# 01_Panel.net
KiCad netlist of a schematic drawn in Altium Designer
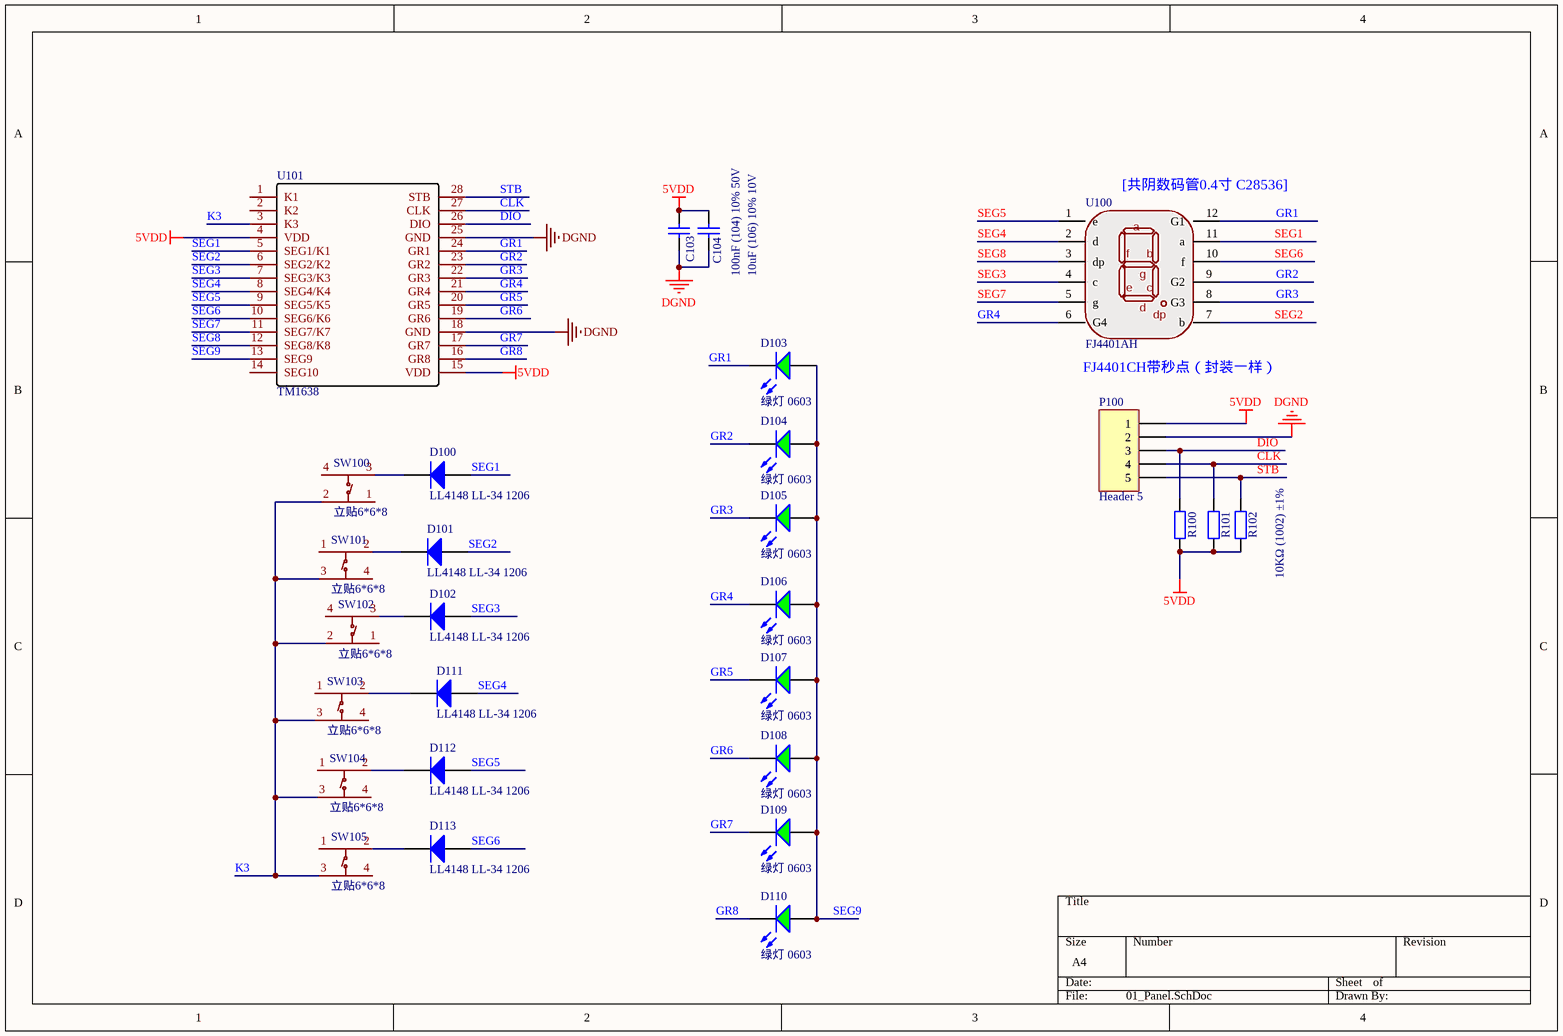
[diagram p0: 01_Panel.SchDoc]

(export (version "E")
  (design (tool "Eeschema 10.0.6"))
  (components
    (comp (ref "C103")
      (value "10uF (106) 10% 10V")
      (footprint "0603_C")
      (description "贴片电容")
      (libsource (lib "Miscellaneous Devices LC") (part "0603 10uF (106) 10% 10V"))
    )
    (comp (ref "C104")
      (value "100nF (104) 10% 50V")
      (footprint "0603_C")
      (description "贴片电容")
      (libsource (lib "Miscellaneous Devices LC") (part "0603 100nF (104) 10% 50V"))
    )
    (comp (ref "D100")
      (value "LL4148 LL-34 1206")
      (footprint "LL-34")
      (description "开关二极管")
      (libsource (lib "Miscellaneous Devices LC") (part "LL-34 LL4148 LL-34 1206"))
    )
    (comp (ref "D101")
      (value "LL4148 LL-34 1206")
      (footprint "LL-34")
      (description "开关二极管")
      (libsource (lib "Miscellaneous Devices LC") (part "LL-34 LL4148 LL-34 1206"))
    )
    (comp (ref "D102")
      (value "LL4148 LL-34 1206")
      (footprint "LL-34")
      (description "开关二极管")
      (libsource (lib "Miscellaneous Devices LC") (part "LL-34 LL4148 LL-34 1206"))
    )
    (comp (ref "D103")
      (value "绿灯 0603")
      (footprint "LED插件--3mm")
      (description "发光二极管")
      (libsource (lib "Miscellaneous Devices LC") (part "0603 绿灯"))
    )
    (comp (ref "D104")
      (value "绿灯 0603")
      (footprint "LED插件--3mm")
      (description "发光二极管")
      (libsource (lib "Miscellaneous Devices LC") (part "0603 绿灯"))
    )
    (comp (ref "D105")
      (value "绿灯 0603")
      (footprint "LED插件--3mm")
      (description "发光二极管")
      (libsource (lib "Miscellaneous Devices LC") (part "0603 绿灯"))
    )
    (comp (ref "D106")
      (value "绿灯 0603")
      (footprint "LED插件--3mm")
      (description "发光二极管")
      (libsource (lib "Miscellaneous Devices LC") (part "0603 绿灯"))
    )
    (comp (ref "D107")
      (value "绿灯 0603")
      (footprint "LED插件--3mm")
      (description "发光二极管")
      (libsource (lib "Miscellaneous Devices LC") (part "0603 绿灯"))
    )
    (comp (ref "D108")
      (value "绿灯 0603")
      (footprint "LED插件--3mm")
      (description "发光二极管")
      (libsource (lib "Miscellaneous Devices LC") (part "0603 绿灯"))
    )
    (comp (ref "D109")
      (value "绿灯 0603")
      (footprint "LED插件--3mm")
      (description "发光二极管")
      (libsource (lib "Miscellaneous Devices LC") (part "0603 绿灯"))
    )
    (comp (ref "D110")
      (value "绿灯 0603")
      (footprint "LED插件--3mm")
      (description "发光二极管")
      (libsource (lib "Miscellaneous Devices LC") (part "0603 绿灯"))
    )
    (comp (ref "D111")
      (value "LL4148 LL-34 1206")
      (footprint "LL-34")
      (description "开关二极管")
      (libsource (lib "Miscellaneous Devices LC") (part "LL-34 LL4148 LL-34 1206"))
    )
    (comp (ref "D112")
      (value "LL4148 LL-34 1206")
      (footprint "LL-34")
      (description "开关二极管")
      (libsource (lib "Miscellaneous Devices LC") (part "LL-34 LL4148 LL-34 1206"))
    )
    (comp (ref "D113")
      (value "LL4148 LL-34 1206")
      (footprint "LL-34")
      (description "开关二极管")
      (libsource (lib "Miscellaneous Devices LC") (part "LL-34 LL4148 LL-34 1206"))
    )
    (comp (ref "P100")
      (value "Header 5")
      (footprint "XH2.54-5P")
      (description "Header, 5-Pin")
      (fields (field (name "PUBLISHER") "Altium Limited"))
      (libsource (lib "Miscellaneous Connectors") (part "Header 5"))
    )
    (comp (ref "R100")
      (value "10KΩ (1002) ±1%")
      (footprint "0603_R")
      (description "贴片电阻")
      (libsource (lib "Miscellaneous Devices LC") (part "0603 10KΩ (1002) 1%"))
    )
    (comp (ref "R101")
      (value "10KΩ (1002) ±1%")
      (footprint "0603_R")
      (description "贴片电阻")
      (libsource (lib "Miscellaneous Devices LC") (part "0603 10KΩ (1002) 1%"))
    )
    (comp (ref "R102")
      (value "10KΩ (1002) ±1%")
      (footprint "0603_R")
      (description "贴片电阻")
      (libsource (lib "Miscellaneous Devices LC") (part "0603 10KΩ (1002) 1%"))
    )
    (comp (ref "SW100") (value "立贴6*6*8") (footprint "SW") (libsource (lib "RayPCB20210502") (part "SW")))
    (comp (ref "SW101") (value "立贴6*6*8") (footprint "SW") (libsource (lib "RayPCB20210502") (part "SW")))
    (comp (ref "SW102") (value "立贴6*6*8") (footprint "SW") (libsource (lib "RayPCB20210502") (part "SW")))
    (comp (ref "SW103") (value "立贴6*6*8") (footprint "SW") (libsource (lib "RayPCB20210502") (part "SW")))
    (comp (ref "SW104") (value "立贴6*6*8") (footprint "SW") (libsource (lib "RayPCB20210502") (part "SW")))
    (comp (ref "SW105") (value "立贴6*6*8") (footprint "SW") (libsource (lib "RayPCB20210502") (part "SW")))
    (comp (ref "U100")
      (value "FJ4401AH")
      (footprint "Digital_0.4")
      (libsource (lib "Schlibv2") (part "Digital_0.4"))
    )
    (comp (ref "U101") (value "TM1638") (footprint "TM1638") (libsource (lib "Schlibv2") (part "TM1638")))
  )
  (nets
    (net (code "1") (name "/CLK") (class "Default")
      (node (ref "P100") (pin "4") (pinfunction "4_4") (pintype "passive"))
      (node (ref "R101") (pin "2") (pinfunction "2_2") (pintype "passive"))
      (node (ref "U101") (pin "27") (pinfunction "CLK_27") (pintype "passive"))
    )
    (net (code "2") (name "/DIO") (class "Default")
      (node (ref "P100") (pin "3") (pinfunction "3_3") (pintype "passive"))
      (node (ref "R100") (pin "2") (pinfunction "2_2") (pintype "passive"))
      (node (ref "U101") (pin "26") (pinfunction "DIO_26") (pintype "passive"))
    )
    (net (code "3") (name "/GR1") (class "Default")
      (node (ref "D103") (pin "K") (pinfunction "K_K") (pintype "passive"))
      (node (ref "U100") (pin "12") (pinfunction "G1_12") (pintype "passive"))
      (node (ref "U101") (pin "24") (pinfunction "GR1_24") (pintype "passive"))
    )
    (net (code "4") (name "/GR2") (class "Default")
      (node (ref "D104") (pin "K") (pinfunction "K_K") (pintype "passive"))
      (node (ref "U100") (pin "9") (pinfunction "G2_9") (pintype "passive"))
      (node (ref "U101") (pin "23") (pinfunction "GR2_23") (pintype "passive"))
    )
    (net (code "5") (name "/GR3") (class "Default")
      (node (ref "D105") (pin "K") (pinfunction "K_K") (pintype "passive"))
      (node (ref "U100") (pin "8") (pinfunction "G3_8") (pintype "passive"))
      (node (ref "U101") (pin "22") (pinfunction "GR3_22") (pintype "passive"))
    )
    (net (code "6") (name "/GR4") (class "Default")
      (node (ref "D106") (pin "K") (pinfunction "K_K") (pintype "passive"))
      (node (ref "U100") (pin "6") (pinfunction "G4_6") (pintype "passive"))
      (node (ref "U101") (pin "21") (pinfunction "GR4_21") (pintype "passive"))
    )
    (net (code "7") (name "/GR5") (class "Default")
      (node (ref "D107") (pin "K") (pinfunction "K_K") (pintype "passive"))
      (node (ref "U101") (pin "20") (pinfunction "GR5_20") (pintype "passive"))
    )
    (net (code "8") (name "/GR6") (class "Default")
      (node (ref "D108") (pin "K") (pinfunction "K_K") (pintype "passive"))
      (node (ref "U101") (pin "19") (pinfunction "GR6_19") (pintype "passive"))
    )
    (net (code "9") (name "/GR7") (class "Default")
      (node (ref "D109") (pin "K") (pinfunction "K_K") (pintype "passive"))
      (node (ref "U101") (pin "17") (pinfunction "GR7_17") (pintype "passive"))
    )
    (net (code "10") (name "/GR8") (class "Default")
      (node (ref "D110") (pin "K") (pinfunction "K_K") (pintype "passive"))
      (node (ref "U101") (pin "16") (pinfunction "GR8_16") (pintype "passive"))
    )
    (net (code "11") (name "/K3") (class "Default")
      (node (ref "SW100") (pin "2") (pinfunction "2_2") (pintype "passive"))
      (node (ref "SW101") (pin "3") (pinfunction "3_3") (pintype "passive"))
      (node (ref "SW102") (pin "2") (pinfunction "2_2") (pintype "passive"))
      (node (ref "SW103") (pin "3") (pinfunction "3_3") (pintype "passive"))
      (node (ref "SW104") (pin "3") (pinfunction "3_3") (pintype "passive"))
      (node (ref "SW105") (pin "3") (pinfunction "3_3") (pintype "passive"))
      (node (ref "U101") (pin "3") (pinfunction "K3_3") (pintype "passive"))
    )
    (net (code "12") (name "/SEG1") (class "Default")
      (node (ref "D100") (pin "1") (pinfunction "A_1") (pintype "passive"))
      (node (ref "U100") (pin "11") (pinfunction "a_11") (pintype "passive"))
      (node (ref "U101") (pin "5") (pinfunction "SEG1/K1_5") (pintype "passive"))
    )
    (net (code "13") (name "/SEG2") (class "Default")
      (node (ref "D101") (pin "1") (pinfunction "A_1") (pintype "passive"))
      (node (ref "U100") (pin "7") (pinfunction "b_7") (pintype "passive"))
      (node (ref "U101") (pin "6") (pinfunction "SEG2/K2_6") (pintype "passive"))
    )
    (net (code "14") (name "/SEG3") (class "Default")
      (node (ref "D102") (pin "1") (pinfunction "A_1") (pintype "passive"))
      (node (ref "U100") (pin "4") (pinfunction "c_4") (pintype "passive"))
      (node (ref "U101") (pin "7") (pinfunction "SEG3/K3_7") (pintype "passive"))
    )
    (net (code "15") (name "/SEG4") (class "Default")
      (node (ref "D111") (pin "1") (pinfunction "A_1") (pintype "passive"))
      (node (ref "U100") (pin "2") (pinfunction "d_2") (pintype "passive"))
      (node (ref "U101") (pin "8") (pinfunction "SEG4/K4_8") (pintype "passive"))
    )
    (net (code "16") (name "/SEG5") (class "Default")
      (node (ref "D112") (pin "1") (pinfunction "A_1") (pintype "passive"))
      (node (ref "U100") (pin "1") (pinfunction "e_1") (pintype "passive"))
      (node (ref "U101") (pin "9") (pinfunction "SEG5/K5_9") (pintype "passive"))
    )
    (net (code "17") (name "/SEG6") (class "Default")
      (node (ref "D113") (pin "1") (pinfunction "A_1") (pintype "passive"))
      (node (ref "U100") (pin "10") (pinfunction "f_10") (pintype "passive"))
      (node (ref "U101") (pin "10") (pinfunction "SEG6/K6_10") (pintype "passive"))
    )
    (net (code "18") (name "/SEG7") (class "Default")
      (node (ref "U100") (pin "5") (pinfunction "g_5") (pintype "passive"))
      (node (ref "U101") (pin "11") (pinfunction "SEG7/K7_11") (pintype "passive"))
    )
    (net (code "19") (name "/SEG8") (class "Default")
      (node (ref "U100") (pin "3") (pinfunction "dp_3") (pintype "passive"))
      (node (ref "U101") (pin "12") (pinfunction "SEG8/K8_12") (pintype "passive"))
    )
    (net (code "20") (name "/SEG9") (class "Default")
      (node (ref "D103") (pin "A") (pinfunction "A_A") (pintype "passive"))
      (node (ref "D104") (pin "A") (pinfunction "A_A") (pintype "passive"))
      (node (ref "D105") (pin "A") (pinfunction "A_A") (pintype "passive"))
      (node (ref "D106") (pin "A") (pinfunction "A_A") (pintype "passive"))
      (node (ref "D107") (pin "A") (pinfunction "A_A") (pintype "passive"))
      (node (ref "D108") (pin "A") (pinfunction "A_A") (pintype "passive"))
      (node (ref "D109") (pin "A") (pinfunction "A_A") (pintype "passive"))
      (node (ref "D110") (pin "A") (pinfunction "A_A") (pintype "passive"))
      (node (ref "U101") (pin "13") (pinfunction "SEG9_13") (pintype "passive"))
    )
    (net (code "21") (name "/STB") (class "Default")
      (node (ref "P100") (pin "5") (pinfunction "5_5") (pintype "passive"))
      (node (ref "R102") (pin "2") (pinfunction "2_2") (pintype "passive"))
      (node (ref "U101") (pin "28") (pinfunction "STB_28") (pintype "passive"))
    )
    (net (code "22") (name "5VDD") (class "Default")
      (node (ref "C103") (pin "2") (pinfunction "2_2") (pintype "passive"))
      (node (ref "C104") (pin "2") (pinfunction "2_2") (pintype "passive"))
      (node (ref "P100") (pin "1") (pinfunction "1_1") (pintype "passive"))
      (node (ref "R100") (pin "1") (pinfunction "1_1") (pintype "passive"))
      (node (ref "R101") (pin "1") (pinfunction "1_1") (pintype "passive"))
      (node (ref "R102") (pin "1") (pinfunction "1_1") (pintype "passive"))
      (node (ref "U101") (pin "15") (pinfunction "VDD_15") (pintype "passive"))
      (node (ref "U101") (pin "4") (pinfunction "VDD_4") (pintype "passive"))
    )
    (net (code "23") (name "DGND") (class "Default")
      (node (ref "C103") (pin "1") (pinfunction "1_1") (pintype "passive"))
      (node (ref "C104") (pin "1") (pinfunction "1_1") (pintype "passive"))
      (node (ref "P100") (pin "2") (pinfunction "2_2") (pintype "passive"))
      (node (ref "U101") (pin "18") (pinfunction "GND_18") (pintype "passive"))
      (node (ref "U101") (pin "25") (pinfunction "GND_25") (pintype "passive"))
    )
    (net (code "24") (name "Net-(D100-K)") (class "Default")
      (node (ref "D100") (pin "2") (pinfunction "K_2") (pintype "passive"))
      (node (ref "SW100") (pin "3") (pinfunction "3_3") (pintype "passive"))
    )
    (net (code "25") (name "Net-(D101-K)") (class "Default")
      (node (ref "D101") (pin "2") (pinfunction "K_2") (pintype "passive"))
      (node (ref "SW101") (pin "2") (pinfunction "2_2") (pintype "passive"))
    )
    (net (code "26") (name "Net-(D102-K)") (class "Default")
      (node (ref "D102") (pin "2") (pinfunction "K_2") (pintype "passive"))
      (node (ref "SW102") (pin "3") (pinfunction "3_3") (pintype "passive"))
    )
    (net (code "27") (name "Net-(D111-K)") (class "Default")
      (node (ref "D111") (pin "2") (pinfunction "K_2") (pintype "passive"))
      (node (ref "SW103") (pin "2") (pinfunction "2_2") (pintype "passive"))
    )
    (net (code "28") (name "Net-(D112-K)") (class "Default")
      (node (ref "D112") (pin "2") (pinfunction "K_2") (pintype "passive"))
      (node (ref "SW104") (pin "2") (pinfunction "2_2") (pintype "passive"))
    )
    (net (code "29") (name "Net-(D113-K)") (class "Default")
      (node (ref "D113") (pin "2") (pinfunction "K_2") (pintype "passive"))
      (node (ref "SW105") (pin "2") (pinfunction "2_2") (pintype "passive"))
    )
    (net (code "30") (name "unconnected-(SW100-Pad1)") (class "Default")
      (node (ref "SW100") (pin "1") (pinfunction "1_1") (pintype "passive"))
    )
    (net (code "31") (name "unconnected-(SW100-Pad4)") (class "Default")
      (node (ref "SW100") (pin "4") (pinfunction "4_4") (pintype "passive"))
    )
    (net (code "32") (name "unconnected-(SW101-Pad1)") (class "Default")
      (node (ref "SW101") (pin "1") (pinfunction "1_1") (pintype "passive"))
    )
    (net (code "33") (name "unconnected-(SW101-Pad4)") (class "Default")
      (node (ref "SW101") (pin "4") (pinfunction "4_4") (pintype "passive"))
    )
    (net (code "34") (name "unconnected-(SW102-Pad1)") (class "Default")
      (node (ref "SW102") (pin "1") (pinfunction "1_1") (pintype "passive"))
    )
    (net (code "35") (name "unconnected-(SW102-Pad4)") (class "Default")
      (node (ref "SW102") (pin "4") (pinfunction "4_4") (pintype "passive"))
    )
    (net (code "36") (name "unconnected-(SW103-Pad1)") (class "Default")
      (node (ref "SW103") (pin "1") (pinfunction "1_1") (pintype "passive"))
    )
    (net (code "37") (name "unconnected-(SW103-Pad4)") (class "Default")
      (node (ref "SW103") (pin "4") (pinfunction "4_4") (pintype "passive"))
    )
    (net (code "38") (name "unconnected-(SW104-Pad1)") (class "Default")
      (node (ref "SW104") (pin "1") (pinfunction "1_1") (pintype "passive"))
    )
    (net (code "39") (name "unconnected-(SW104-Pad4)") (class "Default")
      (node (ref "SW104") (pin "4") (pinfunction "4_4") (pintype "passive"))
    )
    (net (code "40") (name "unconnected-(SW105-Pad1)") (class "Default")
      (node (ref "SW105") (pin "1") (pinfunction "1_1") (pintype "passive"))
    )
    (net (code "41") (name "unconnected-(SW105-Pad4)") (class "Default")
      (node (ref "SW105") (pin "4") (pinfunction "4_4") (pintype "passive"))
    )
    (net (code "42") (name "unconnected-(U101-K1-Pad1)") (class "Default")
      (node (ref "U101") (pin "1") (pinfunction "K1_1") (pintype "passive"))
    )
    (net (code "43") (name "unconnected-(U101-K2-Pad2)") (class "Default")
      (node (ref "U101") (pin "2") (pinfunction "K2_2") (pintype "passive"))
    )
    (net (code "44") (name "unconnected-(U101-SEG10-Pad14)") (class "Default")
      (node (ref "U101") (pin "14") (pinfunction "SEG10_14") (pintype "passive"))
    )
  )
)
